# solarCharger.net
KiCad netlist of a schematic drawn in EAGLE
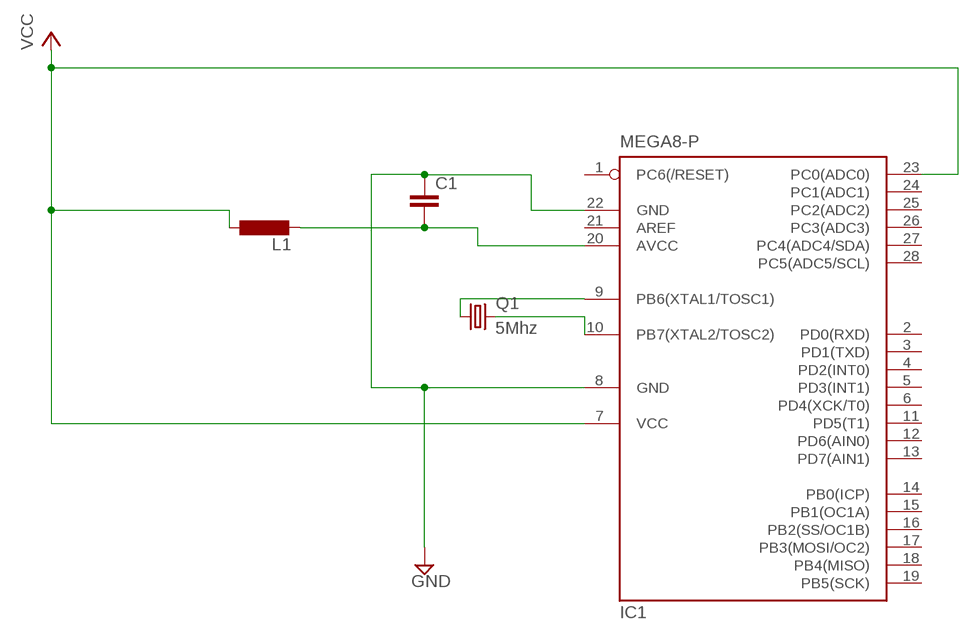
[diagram p0: schematic, sheet 1]

(export (version "E")
  (design (tool "Eeschema 10.0.6"))
  (components
    (comp (ref "C1")
      (value "C2,5-3")
      (footprint "eagle-import:C2.5-3")
      (libsource (lib "eagle-import") (part "C2,5-3"))
    )
    (comp (ref "IC1")
      (value "MEGA8-P")
      (footprint "eagle-import:DIL28-3")
      (libsource (lib "eagle-import") (part "MEGA8-P"))
    )
    (comp (ref "L1")
      (value "L-EU0204/5")
      (footprint "eagle-import:0204_5")
      (libsource (lib "eagle-import") (part "L-EU0204/5"))
    )
    (comp (ref "Q1")
      (value "5Mhz")
      (footprint "eagle-import:HC49_S")
      (libsource (lib "eagle-import") (part "CRYSTALHC49S"))
    )
  )
  (nets
    (net (code "1") (name "GND") (class "Default")
      (node (ref "C1") (pin "1") (pinfunction "1_1") (pintype "passive"))
      (node (ref "IC1") (pin "22") (pinfunction "GND_22") (pintype "power_in"))
      (node (ref "IC1") (pin "8") (pinfunction "GND_8") (pintype "power_in"))
    )
    (net (code "2") (name "Net-(IC1-AVCC)") (class "Default")
      (node (ref "C1") (pin "2") (pinfunction "2_2") (pintype "passive"))
      (node (ref "IC1") (pin "20") (pinfunction "AVCC_20") (pintype "power_in"))
      (node (ref "L1") (pin "2") (pinfunction "2_2") (pintype "passive"))
    )
    (net (code "3") (name "Net-(IC1-PB6(XTAL1{slash}TOSC1))") (class "Default")
      (node (ref "IC1") (pin "9") (pinfunction "PB6(XTAL1/TOSC1)_9") (pintype "bidirectional"))
      (node (ref "Q1") (pin "1") (pinfunction "1_1") (pintype "passive"))
    )
    (net (code "4") (name "Net-(IC1-PB7(XTAL2{slash}TOSC2))") (class "Default")
      (node (ref "IC1") (pin "10") (pinfunction "PB7(XTAL2/TOSC2)_10") (pintype "bidirectional"))
      (node (ref "Q1") (pin "2") (pinfunction "2_2") (pintype "passive"))
    )
    (net (code "5") (name "VCC") (class "Default")
      (node (ref "IC1") (pin "23") (pinfunction "PC0(ADC0)_23") (pintype "bidirectional"))
      (node (ref "IC1") (pin "7") (pinfunction "VCC_7") (pintype "power_in"))
      (node (ref "L1") (pin "1") (pinfunction "1_1") (pintype "passive"))
    )
    (net (code "6") (name "unconnected-(IC1-AREF-Pad21)") (class "Default")
      (node (ref "IC1") (pin "21") (pinfunction "AREF_21") (pintype "passive"))
    )
    (net (code "7") (name "unconnected-(IC1-PB0(ICP)-Pad14)") (class "Default")
      (node (ref "IC1") (pin "14") (pinfunction "PB0(ICP)_14") (pintype "bidirectional"))
    )
    (net (code "8") (name "unconnected-(IC1-PB1(OC1A)-Pad15)") (class "Default")
      (node (ref "IC1") (pin "15") (pinfunction "PB1(OC1A)_15") (pintype "bidirectional"))
    )
    (net (code "9") (name "unconnected-(IC1-PB2(SS{slash}OC1B)-Pad16)") (class "Default")
      (node (ref "IC1") (pin "16") (pinfunction "PB2(SS/OC1B)_16") (pintype "bidirectional"))
    )
    (net (code "10") (name "unconnected-(IC1-PB3(MOSI{slash}OC2)-Pad17)") (class "Default")
      (node (ref "IC1") (pin "17") (pinfunction "PB3(MOSI/OC2)_17") (pintype "bidirectional"))
    )
    (net (code "11") (name "unconnected-(IC1-PB4(MISO)-Pad18)") (class "Default")
      (node (ref "IC1") (pin "18") (pinfunction "PB4(MISO)_18") (pintype "bidirectional"))
    )
    (net (code "12") (name "unconnected-(IC1-PB5(SCK)-Pad19)") (class "Default")
      (node (ref "IC1") (pin "19") (pinfunction "PB5(SCK)_19") (pintype "bidirectional"))
    )
    (net (code "13") (name "unconnected-(IC1-PC1(ADC1)-Pad24)") (class "Default")
      (node (ref "IC1") (pin "24") (pinfunction "PC1(ADC1)_24") (pintype "bidirectional"))
    )
    (net (code "14") (name "unconnected-(IC1-PC2(ADC2)-Pad25)") (class "Default")
      (node (ref "IC1") (pin "25") (pinfunction "PC2(ADC2)_25") (pintype "bidirectional"))
    )
    (net (code "15") (name "unconnected-(IC1-PC3(ADC3)-Pad26)") (class "Default")
      (node (ref "IC1") (pin "26") (pinfunction "PC3(ADC3)_26") (pintype "bidirectional"))
    )
    (net (code "16") (name "unconnected-(IC1-PC4(ADC4{slash}SDA)-Pad27)") (class "Default")
      (node (ref "IC1") (pin "27") (pinfunction "PC4(ADC4/SDA)_27") (pintype "bidirectional"))
    )
    (net (code "17") (name "unconnected-(IC1-PC5(ADC5{slash}SCL)-Pad28)") (class "Default")
      (node (ref "IC1") (pin "28") (pinfunction "PC5(ADC5/SCL)_28") (pintype "bidirectional"))
    )
    (net (code "18") (name "unconnected-(IC1-PC6({slash}RESET)-Pad1)") (class "Default")
      (node (ref "IC1") (pin "1") (pinfunction "PC6(/RESET)_1") (pintype "bidirectional"))
    )
    (net (code "19") (name "unconnected-(IC1-PD0(RXD)-Pad2)") (class "Default")
      (node (ref "IC1") (pin "2") (pinfunction "PD0(RXD)_2") (pintype "bidirectional"))
    )
    (net (code "20") (name "unconnected-(IC1-PD1(TXD)-Pad3)") (class "Default")
      (node (ref "IC1") (pin "3") (pinfunction "PD1(TXD)_3") (pintype "bidirectional"))
    )
    (net (code "21") (name "unconnected-(IC1-PD2(INT0)-Pad4)") (class "Default")
      (node (ref "IC1") (pin "4") (pinfunction "PD2(INT0)_4") (pintype "bidirectional"))
    )
    (net (code "22") (name "unconnected-(IC1-PD3(INT1)-Pad5)") (class "Default")
      (node (ref "IC1") (pin "5") (pinfunction "PD3(INT1)_5") (pintype "bidirectional"))
    )
    (net (code "23") (name "unconnected-(IC1-PD4(XCK{slash}T0)-Pad6)") (class "Default")
      (node (ref "IC1") (pin "6") (pinfunction "PD4(XCK/T0)_6") (pintype "bidirectional"))
    )
    (net (code "24") (name "unconnected-(IC1-PD5(T1)-Pad11)") (class "Default")
      (node (ref "IC1") (pin "11") (pinfunction "PD5(T1)_11") (pintype "bidirectional"))
    )
    (net (code "25") (name "unconnected-(IC1-PD6(AIN0)-Pad12)") (class "Default")
      (node (ref "IC1") (pin "12") (pinfunction "PD6(AIN0)_12") (pintype "bidirectional"))
    )
    (net (code "26") (name "unconnected-(IC1-PD7(AIN1)-Pad13)") (class "Default")
      (node (ref "IC1") (pin "13") (pinfunction "PD7(AIN1)_13") (pintype "bidirectional"))
    )
  )
)
